# Stepper_Driver_Board.net
KiCad netlist of a schematic drawn in EAGLE
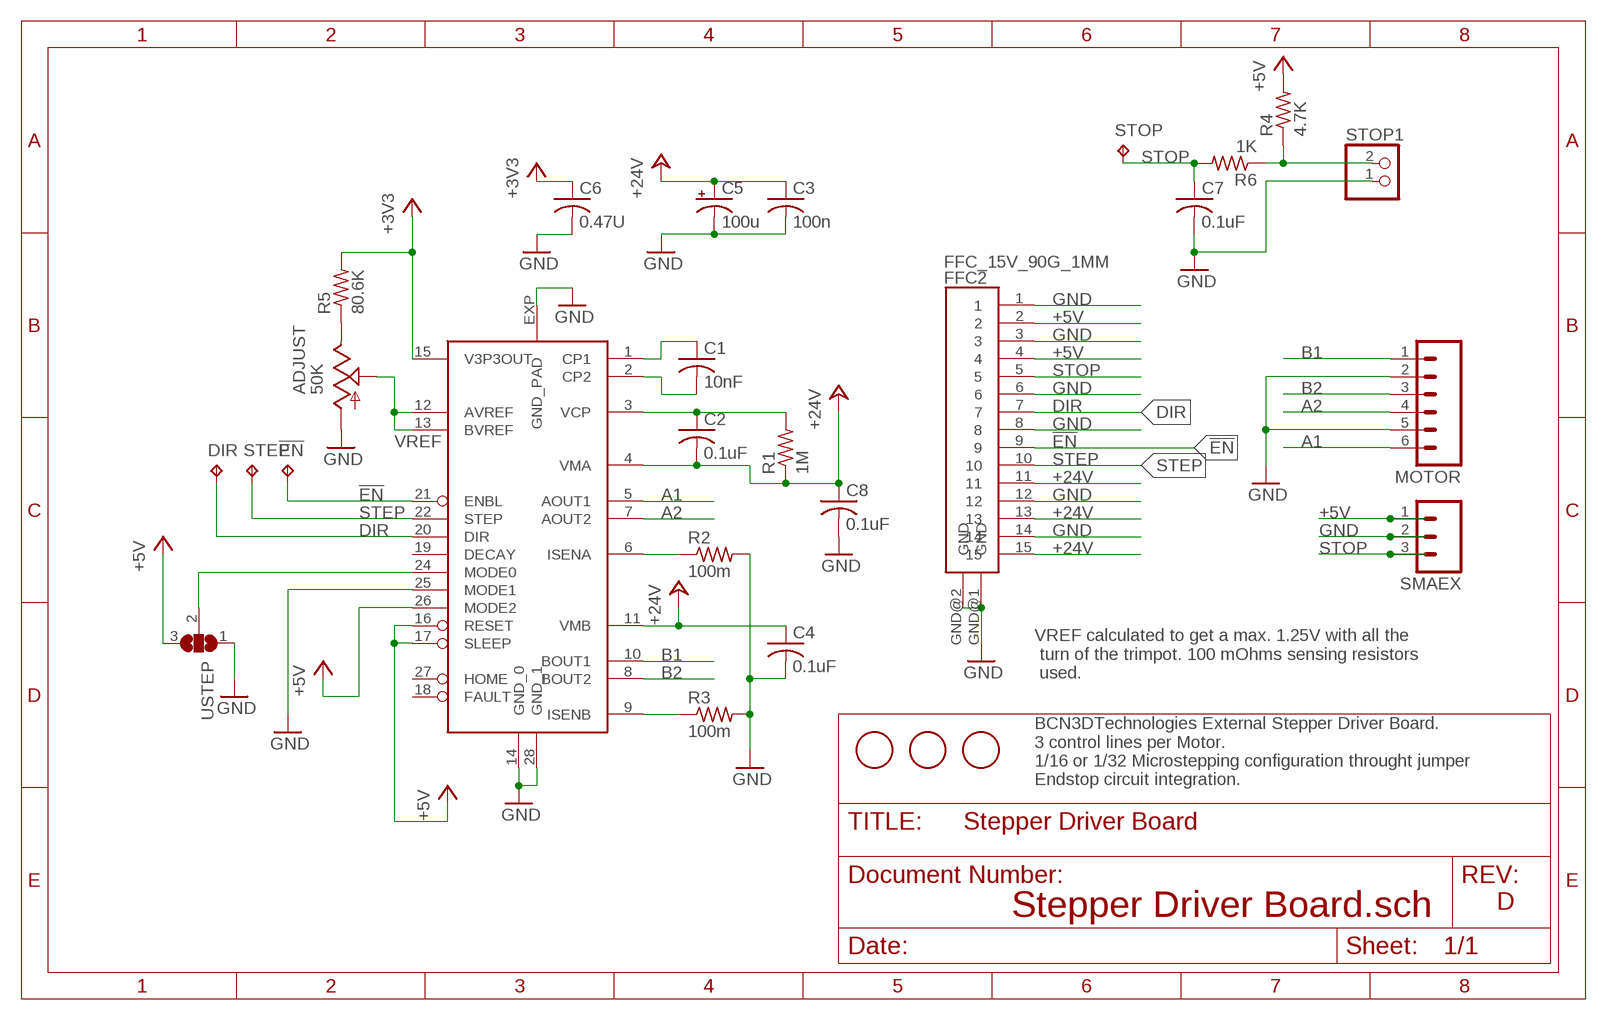
[diagram p0: schematic, sheet 1]

(export (version "E")
  (design (tool "Eeschema 10.0.6"))
  (components
    (comp (ref "!EN")
      (value "TPB1,27")
      (footprint "eagle-import:B1,27")
      (libsource (lib "eagle-import") (part "TPB1,27"))
    )
    (comp (ref "ADJUST")
      (value "50K")
      (footprint "eagle-import:3223G")
      (fields (field (name "MF") "BOURNS") (field (name "MPN") "TC33X-2-503E"))
      (libsource (lib "eagle-import") (part "TRIM_US-3223G"))
    )
    (comp (ref "C1")
      (value "10nF")
      (footprint "eagle-import:C0805")
      (fields (field (name "MF") "AVX") (field (name "MPN") "06035C103JAT2A"))
      (libsource (lib "eagle-import") (part "C-USC0805"))
    )
    (comp (ref "C2")
      (value "0.1uF")
      (footprint "eagle-import:C0805")
      (fields (field (name "MF") "AVX") (field (name "MPN") "08055C104K4Z2A"))
      (libsource (lib "eagle-import") (part "C-USC0805"))
    )
    (comp (ref "C3")
      (value "100n")
      (footprint "eagle-import:C0805")
      (fields (field (name "MF") "AVX") (field (name "MPN") "08055C104K4Z2A"))
      (libsource (lib "eagle-import") (part "C-USC0805"))
    )
    (comp (ref "C4")
      (value "0.1uF")
      (footprint "eagle-import:C0805")
      (fields (field (name "MF") "AVX") (field (name "MPN") "08055C104K4Z2A"))
      (libsource (lib "eagle-import") (part "C-USC0805"))
    )
    (comp (ref "C5")
      (value "100u")
      (footprint "eagle-import:UD-6,3X7,7_NICHICON")
      (fields (field (name "MF") "PANASONIC ELECTRONIC COMPONENTS") (field (name "MPN") "EEE1HA101UAP"))
      (libsource (lib "eagle-import") (part "CPOL-USUD-6,3X7,7"))
    )
    (comp (ref "C6")
      (value "0.47U")
      (footprint "eagle-import:C0805")
      (fields (field (name "MF") "KEMET") (field (name "MPN") "C0805C474K5RACTU"))
      (libsource (lib "eagle-import") (part "C-USC0805"))
    )
    (comp (ref "C7")
      (value "0.1uF")
      (footprint "eagle-import:C0805")
      (fields (field (name "MF") "AVX") (field (name "MPN") "08055C104K4Z2A"))
      (libsource (lib "eagle-import") (part "C-USC0805"))
    )
    (comp (ref "C8")
      (value "0.1uF")
      (footprint "eagle-import:C0805")
      (fields (field (name "MF") "AVX") (field (name "MPN") "08055C104K4Z2A"))
      (libsource (lib "eagle-import") (part "C-USC0805"))
    )
    (comp (ref "DIR")
      (value "TPB1,27")
      (footprint "eagle-import:B1,27")
      (libsource (lib "eagle-import") (part "TPB1,27"))
    )
    (comp (ref "FFC2")
      (value "FFC_15V_90G_1MM")
      (footprint "eagle-import:TE_FFC_CON1MM")
      (libsource (lib "eagle-import") (part "FFC_15V_90G_1MM"))
    )
    (comp (ref "IC1")
      (value "DRV8825PWP")
      (footprint "eagle-import:TSSOP-28")
      (fields (field (name "MF") "TEXAS INSTRUMENTS"))
      (libsource (lib "eagle-import") (part "DRV8825PWP"))
    )
    (comp (ref "MOTOR")
      (value "M06")
      (footprint "eagle-import:JST-6-PTH")
      (libsource (lib "eagle-import") (part "M06"))
    )
    (comp (ref "R1")
      (value "1M")
      (footprint "eagle-import:R0805")
      (fields (field (name "MF") "MULTICOMP") (field (name "MPN") "MC0805S8F1004T5E"))
      (libsource (lib "eagle-import") (part "R-US_R0805"))
    )
    (comp (ref "R2")
      (value "100m")
      (footprint "eagle-import:R1210")
      (fields (field (name "MF") "PANASONIC ELECTRONIC COMPONENTS") (field (name "MPN") "ERJ14BSFR10U"))
      (libsource (lib "eagle-import") (part "R-US_R1210"))
    )
    (comp (ref "R3")
      (value "100m")
      (footprint "eagle-import:R1210")
      (fields (field (name "MF") "PANASONIC ELECTRONIC COMPONENTS") (field (name "MPN") "ERJ14BSFR10U"))
      (libsource (lib "eagle-import") (part "R-US_R1210"))
    )
    (comp (ref "R4")
      (value "4.7K")
      (footprint "eagle-import:R0805")
      (fields (field (name "MF") "PANASONIC ELECTRONIC COMPONENTS") (field (name "MPN") "ERJP06F4701V"))
      (libsource (lib "eagle-import") (part "R-US_R0805"))
    )
    (comp (ref "R5")
      (value "80.6K")
      (footprint "eagle-import:R0805")
      (fields (field (name "MF") "VISHAY DALE") (field (name "MPN") "CRCW080580K6FKEA"))
      (libsource (lib "eagle-import") (part "R-US_R0805"))
    )
    (comp (ref "R6")
      (value "1K")
      (footprint "eagle-import:R0805")
      (fields (field (name "MF") "BOURNS") (field (name "MPN") "CR0805-JW-102ELF"))
      (libsource (lib "eagle-import") (part "R-US_R0805"))
    )
    (comp (ref "SMAEX")
      (value "M03PTH")
      (footprint "eagle-import:1X03")
      (libsource (lib "eagle-import") (part "M03PTH"))
    )
    (comp (ref "STEP")
      (value "TPB1,27")
      (footprint "eagle-import:B1,27")
      (libsource (lib "eagle-import") (part "TPB1,27"))
    )
    (comp (ref "STOP")
      (value "TPB1,27")
      (footprint "eagle-import:B1,27")
      (libsource (lib "eagle-import") (part "TPB1,27"))
    )
    (comp (ref "STOP1")
      (value "JST_2PIN-THM-RA")
      (footprint "eagle-import:JST-PH-2-THM-RA")
      (libsource (lib "eagle-import") (part "JST_2PIN-THM-RA"))
    )
    (comp (ref "U$2")
      (value "FIDUCIAL")
      (footprint "eagle-import:FIDUCIAL_1MM")
      (libsource (lib "eagle-import") (part "FIDUCIAL"))
    )
    (comp (ref "U$3")
      (value "FIDUCIAL")
      (footprint "eagle-import:FIDUCIAL_1MM")
      (libsource (lib "eagle-import") (part "FIDUCIAL"))
    )
    (comp (ref "U$4")
      (value "FIDUCIAL")
      (footprint "eagle-import:FIDUCIAL_1MM")
      (libsource (lib "eagle-import") (part "FIDUCIAL"))
    )
    (comp (ref "USTEP")
      (value "SJ2W")
      (footprint "eagle-import:SJ_2")
      (libsource (lib "eagle-import") (part "SJ2W"))
    )
  )
  (nets
    (net (code "1") (name "+3V3") (class "Default")
      (node (ref "C6") (pin "1") (pinfunction "1_1") (pintype "passive"))
      (node (ref "IC1") (pin "15") (pinfunction "V3P3OUT_15") (pintype "output"))
      (node (ref "R5") (pin "2") (pinfunction "2_2") (pintype "passive"))
    )
    (net (code "2") (name "+5V") (class "Default")
      (node (ref "FFC2") (pin "2") (pinfunction "2_2") (pintype "bidirectional"))
      (node (ref "FFC2") (pin "4") (pinfunction "4_4") (pintype "bidirectional"))
      (node (ref "IC1") (pin "16") (pinfunction "RESET_16") (pintype "input"))
      (node (ref "IC1") (pin "17") (pinfunction "SLEEP_17") (pintype "input"))
      (node (ref "IC1") (pin "26") (pinfunction "MODE2_26") (pintype "input"))
      (node (ref "R4") (pin "2") (pinfunction "2_2") (pintype "passive"))
      (node (ref "SMAEX") (pin "1") (pinfunction "1_1") (pintype "passive"))
      (node (ref "USTEP") (pin "3") (pinfunction "3_3") (pintype "passive"))
    )
    (net (code "3") (name "+24V") (class "Default")
      (node (ref "C2") (pin "2") (pinfunction "2_2") (pintype "passive"))
      (node (ref "C3") (pin "1") (pinfunction "1_1") (pintype "passive"))
      (node (ref "C4") (pin "1") (pinfunction "1_1") (pintype "passive"))
      (node (ref "C5") (pin "+") (pinfunction "+_+") (pintype "passive"))
      (node (ref "C8") (pin "1") (pinfunction "1_1") (pintype "passive"))
      (node (ref "FFC2") (pin "11") (pinfunction "11_11") (pintype "bidirectional"))
      (node (ref "FFC2") (pin "13") (pinfunction "13_13") (pintype "bidirectional"))
      (node (ref "FFC2") (pin "15") (pinfunction "15_15") (pintype "bidirectional"))
      (node (ref "IC1") (pin "11") (pinfunction "VMB_11") (pintype "power_in"))
      (node (ref "IC1") (pin "4") (pinfunction "VMA_4") (pintype "power_in"))
      (node (ref "R1") (pin "1") (pinfunction "1_1") (pintype "passive"))
    )
    (net (code "4") (name "/A1") (class "Default")
      (node (ref "IC1") (pin "5") (pinfunction "AOUT1_5") (pintype "output"))
      (node (ref "MOTOR") (pin "6") (pinfunction "6_6") (pintype "passive"))
    )
    (net (code "5") (name "/A2") (class "Default")
      (node (ref "IC1") (pin "7") (pinfunction "AOUT2_7") (pintype "output"))
      (node (ref "MOTOR") (pin "4") (pinfunction "4_4") (pintype "passive"))
    )
    (net (code "6") (name "/B1") (class "Default")
      (node (ref "IC1") (pin "10") (pinfunction "BOUT1_10") (pintype "output"))
      (node (ref "MOTOR") (pin "1") (pinfunction "1_1") (pintype "passive"))
    )
    (net (code "7") (name "/B2") (class "Default")
      (node (ref "IC1") (pin "8") (pinfunction "BOUT2_8") (pintype "output"))
      (node (ref "MOTOR") (pin "3") (pinfunction "3_3") (pintype "passive"))
    )
    (net (code "8") (name "/STOP") (class "Default")
      (node (ref "C7") (pin "1") (pinfunction "1_1") (pintype "passive"))
      (node (ref "FFC2") (pin "5") (pinfunction "5_5") (pintype "bidirectional"))
      (node (ref "R6") (pin "2") (pinfunction "2_2") (pintype "passive"))
      (node (ref "SMAEX") (pin "3") (pinfunction "3_3") (pintype "passive"))
      (node (ref "STOP") (pin "TP") (pinfunction "TP_TP") (pintype "input"))
    )
    (net (code "9") (name "/VREF") (class "Default")
      (node (ref "ADJUST") (pin "2") (pinfunction "S_2") (pintype "passive"))
      (node (ref "IC1") (pin "12") (pinfunction "AVREF_12") (pintype "input"))
      (node (ref "IC1") (pin "13") (pinfunction "BVREF_13") (pintype "input"))
    )
    (net (code "10") (name "/~{EN}") (class "Default")
      (node (ref "!EN") (pin "TP") (pinfunction "TP_TP") (pintype "input"))
      (node (ref "FFC2") (pin "9") (pinfunction "9_9") (pintype "bidirectional"))
      (node (ref "IC1") (pin "21") (pinfunction "ENBL_21") (pintype "input"))
    )
    (net (code "11") (name "DIR") (class "Default")
      (node (ref "DIR") (pin "TP") (pinfunction "TP_TP") (pintype "input"))
      (node (ref "FFC2") (pin "7") (pinfunction "7_7") (pintype "bidirectional"))
      (node (ref "IC1") (pin "20") (pinfunction "DIR_20") (pintype "input"))
    )
    (net (code "12") (name "GND") (class "Default")
      (node (ref "ADJUST") (pin "1") (pinfunction "A_1") (pintype "passive"))
      (node (ref "C3") (pin "2") (pinfunction "2_2") (pintype "passive"))
      (node (ref "C4") (pin "2") (pinfunction "2_2") (pintype "passive"))
      (node (ref "C5") (pin "-") (pinfunction "-_-") (pintype "passive"))
      (node (ref "C6") (pin "2") (pinfunction "2_2") (pintype "passive"))
      (node (ref "C7") (pin "2") (pinfunction "2_2") (pintype "passive"))
      (node (ref "C8") (pin "2") (pinfunction "2_2") (pintype "passive"))
      (node (ref "FFC2") (pin "1") (pinfunction "1_1") (pintype "bidirectional"))
      (node (ref "FFC2") (pin "12") (pinfunction "12_12") (pintype "bidirectional"))
      (node (ref "FFC2") (pin "14") (pinfunction "14_14") (pintype "bidirectional"))
      (node (ref "FFC2") (pin "3") (pinfunction "3_3") (pintype "bidirectional"))
      (node (ref "FFC2") (pin "6") (pinfunction "6_6") (pintype "bidirectional"))
      (node (ref "FFC2") (pin "8") (pinfunction "8_8") (pintype "bidirectional"))
      (node (ref "FFC2") (pin "GND@1") (pinfunction "GND_GND@1") (pintype "bidirectional"))
      (node (ref "FFC2") (pin "GND@2") (pinfunction "GND_GND@2") (pintype "bidirectional"))
      (node (ref "IC1") (pin "14") (pinfunction "GND_0_14") (pintype "power_in"))
      (node (ref "IC1") (pin "25") (pinfunction "MODE1_25") (pintype "input"))
      (node (ref "IC1") (pin "28") (pinfunction "GND_1_28") (pintype "power_in"))
      (node (ref "IC1") (pin "EXP") (pinfunction "GND_PAD_EXP") (pintype "power_in"))
      (node (ref "MOTOR") (pin "2") (pinfunction "2_2") (pintype "passive"))
      (node (ref "MOTOR") (pin "5") (pinfunction "5_5") (pintype "passive"))
      (node (ref "R2") (pin "2") (pinfunction "2_2") (pintype "passive"))
      (node (ref "R3") (pin "2") (pinfunction "2_2") (pintype "passive"))
      (node (ref "SMAEX") (pin "2") (pinfunction "2_2") (pintype "passive"))
      (node (ref "STOP1") (pin "1") (pinfunction "2_1") (pintype "passive"))
      (node (ref "USTEP") (pin "1") (pinfunction "1_1") (pintype "passive"))
    )
    (net (code "13") (name "Net-(ADJUST-E)") (class "Default")
      (node (ref "ADJUST") (pin "3") (pinfunction "E_3") (pintype "passive"))
      (node (ref "R5") (pin "1") (pinfunction "1_1") (pintype "passive"))
    )
    (net (code "14") (name "Net-(IC1-CP1)") (class "Default")
      (node (ref "C1") (pin "1") (pinfunction "1_1") (pintype "passive"))
      (node (ref "IC1") (pin "1") (pinfunction "CP1_1") (pintype "bidirectional"))
    )
    (net (code "15") (name "Net-(IC1-CP2)") (class "Default")
      (node (ref "C1") (pin "2") (pinfunction "2_2") (pintype "passive"))
      (node (ref "IC1") (pin "2") (pinfunction "CP2_2") (pintype "bidirectional"))
    )
    (net (code "16") (name "Net-(IC1-ISENA)") (class "Default")
      (node (ref "IC1") (pin "6") (pinfunction "ISENA_6") (pintype "output"))
      (node (ref "R2") (pin "1") (pinfunction "1_1") (pintype "passive"))
    )
    (net (code "17") (name "Net-(IC1-ISENB)") (class "Default")
      (node (ref "IC1") (pin "9") (pinfunction "ISENB_9") (pintype "output"))
      (node (ref "R3") (pin "1") (pinfunction "1_1") (pintype "passive"))
    )
    (net (code "18") (name "Net-(IC1-MODE0)") (class "Default")
      (node (ref "IC1") (pin "24") (pinfunction "MODE0_24") (pintype "input"))
      (node (ref "USTEP") (pin "2") (pinfunction "2_2") (pintype "passive"))
    )
    (net (code "19") (name "Net-(IC1-VCP)") (class "Default")
      (node (ref "C2") (pin "1") (pinfunction "1_1") (pintype "passive"))
      (node (ref "IC1") (pin "3") (pinfunction "VCP_3") (pintype "bidirectional"))
      (node (ref "R1") (pin "2") (pinfunction "2_2") (pintype "passive"))
    )
    (net (code "20") (name "Net-(STOP1-1)") (class "Default")
      (node (ref "R4") (pin "1") (pinfunction "1_1") (pintype "passive"))
      (node (ref "R6") (pin "1") (pinfunction "1_1") (pintype "passive"))
      (node (ref "STOP1") (pin "2") (pinfunction "1_2") (pintype "passive"))
    )
    (net (code "21") (name "STEP") (class "Default")
      (node (ref "FFC2") (pin "10") (pinfunction "10_10") (pintype "bidirectional"))
      (node (ref "IC1") (pin "22") (pinfunction "STEP_22") (pintype "input"))
      (node (ref "STEP") (pin "TP") (pinfunction "TP_TP") (pintype "input"))
    )
    (net (code "22") (name "unconnected-(IC1-DECAY-Pad19)") (class "Default")
      (node (ref "IC1") (pin "19") (pinfunction "DECAY_19") (pintype "input"))
    )
    (net (code "23") (name "unconnected-(IC1-FAULT-Pad18)") (class "Default")
      (node (ref "IC1") (pin "18") (pinfunction "FAULT_18") (pintype "output"))
    )
    (net (code "24") (name "unconnected-(IC1-HOME-Pad27)") (class "Default")
      (node (ref "IC1") (pin "27") (pinfunction "HOME_27") (pintype "output"))
    )
  )
)
